# blahblahVCA.net
KiCad netlist of a schematic drawn in EAGLE
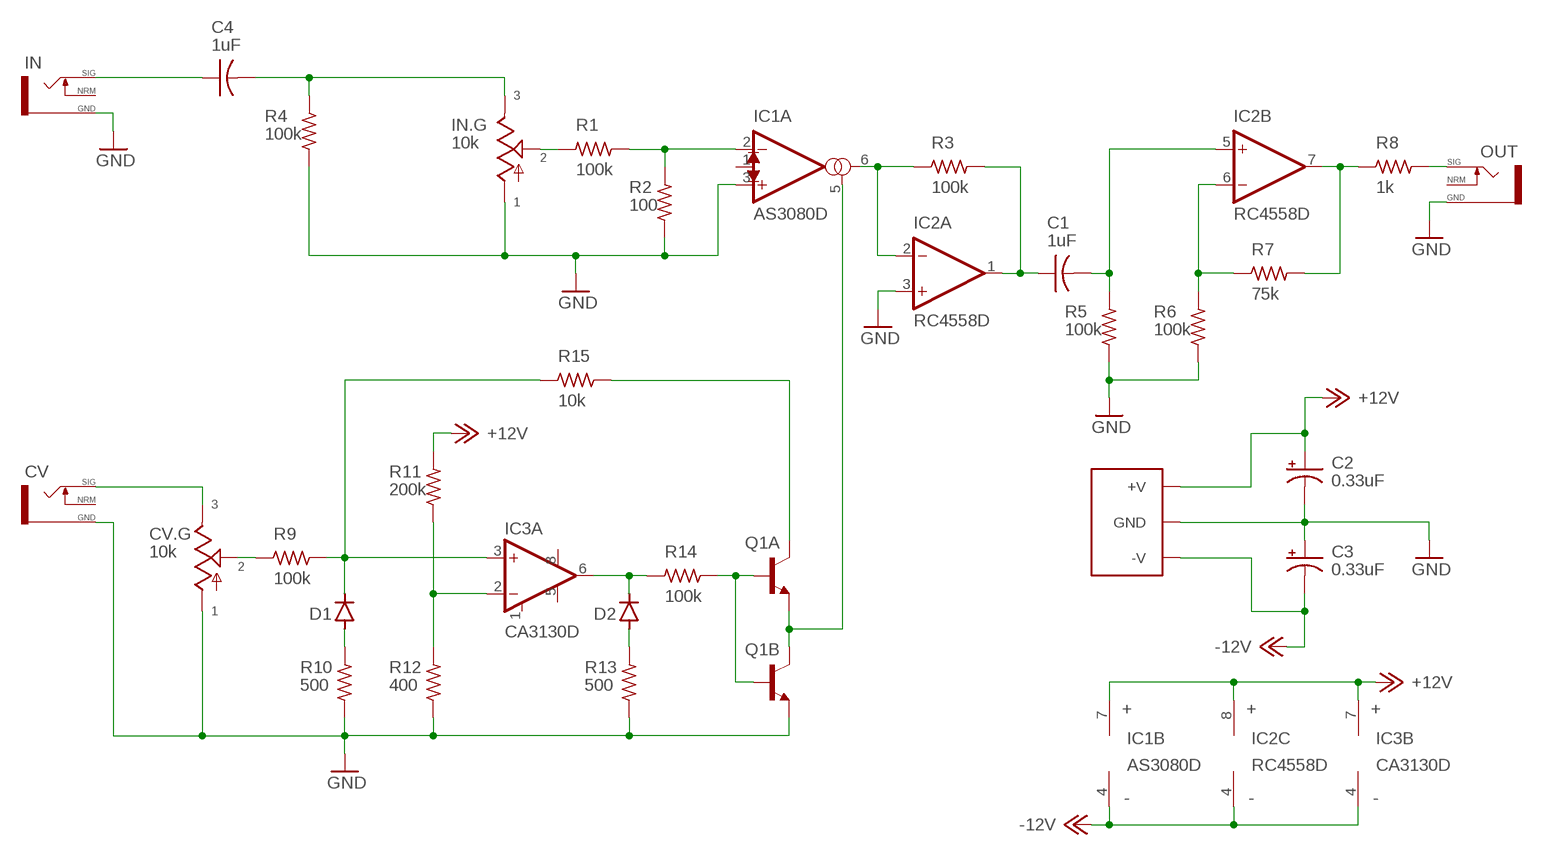
[diagram p0: schematic, sheet 1]

(export (version "E")
  (design (tool "Eeschema 10.0.6"))
  (components
    (comp (ref "C1")
      (value "1uF")
      (footprint "eagle-import:C05")
      (libsource (lib "eagle-import") (part "C-05"))
    )
    (comp (ref "C2")
      (value "0.33uF")
      (footprint "eagle-import:E025")
      (libsource (lib "eagle-import") (part "CPOL-E025"))
    )
    (comp (ref "C3")
      (value "0.33uF")
      (footprint "eagle-import:E025")
      (libsource (lib "eagle-import") (part "CPOL-E025"))
    )
    (comp (ref "C4")
      (value "1uF")
      (footprint "eagle-import:C05")
      (libsource (lib "eagle-import") (part "C-05"))
    )
    (comp (ref "CV")
      (value "MONO301M")
      (footprint "eagle-import:PJ301M")
      (libsource (lib "eagle-import") (part "MONO301M"))
    )
    (comp (ref "CV.G")
      (value "10k")
      (footprint "eagle-import:ALPHA-VERT")
      (libsource (lib "eagle-import") (part "PALPHA"))
    )
    (comp (ref "D1")
      (value "1N914")
      (footprint "eagle-import:DO35-7")
      (libsource (lib "eagle-import") (part "1N914"))
    )
    (comp (ref "D2")
      (value "1N914")
      (footprint "eagle-import:DO35-7")
      (libsource (lib "eagle-import") (part "1N914"))
    )
    (comp (ref "IC1")
      (value "AS3080D")
      (footprint "eagle-import:DIL08")
      (libsource (lib "eagle-import") (part "AS3080D"))
    )
    (comp (ref "IC2")
      (value "RC4558D")
      (footprint "eagle-import:DIL08")
      (libsource (lib "eagle-import") (part "RC4558D"))
    )
    (comp (ref "IC3")
      (value "CA3130D")
      (footprint "eagle-import:DIL08")
      (libsource (lib "eagle-import") (part "CA3130D"))
    )
    (comp (ref "IN")
      (value "MONO301M")
      (footprint "eagle-import:PJ301M")
      (libsource (lib "eagle-import") (part "MONO301M"))
    )
    (comp (ref "IN.G")
      (value "10k")
      (footprint "eagle-import:ALPHA-VERT")
      (libsource (lib "eagle-import") (part "PALPHA"))
    )
    (comp (ref "OUT")
      (value "MONO301M")
      (footprint "eagle-import:PJ301M")
      (libsource (lib "eagle-import") (part "MONO301M"))
    )
    (comp (ref "Q1")
      (value "BCM847DS")
      (footprint "eagle-import:SOT-23-6")
      (libsource (lib "eagle-import") (part "BCM847DS"))
    )
    (comp (ref "R1")
      (value "100k")
      (footprint "eagle-import:R1206")
      (libsource (lib "eagle-import") (part "R-1206"))
    )
    (comp (ref "R2")
      (value "100")
      (footprint "eagle-import:R1206")
      (libsource (lib "eagle-import") (part "R-1206"))
    )
    (comp (ref "R3")
      (value "100k")
      (footprint "eagle-import:R1206")
      (libsource (lib "eagle-import") (part "R-1206"))
    )
    (comp (ref "R4")
      (value "100k")
      (footprint "eagle-import:R1206")
      (libsource (lib "eagle-import") (part "R-1206"))
    )
    (comp (ref "R5")
      (value "100k")
      (footprint "eagle-import:R1206")
      (libsource (lib "eagle-import") (part "R-1206"))
    )
    (comp (ref "R6")
      (value "100k")
      (footprint "eagle-import:R1206")
      (libsource (lib "eagle-import") (part "R-1206"))
    )
    (comp (ref "R7")
      (value "75k")
      (footprint "eagle-import:R1206")
      (libsource (lib "eagle-import") (part "R-1206"))
    )
    (comp (ref "R8")
      (value "1k")
      (footprint "eagle-import:R1206")
      (libsource (lib "eagle-import") (part "R-1206"))
    )
    (comp (ref "R9")
      (value "100k")
      (footprint "eagle-import:R1206")
      (libsource (lib "eagle-import") (part "R-1206"))
    )
    (comp (ref "R10")
      (value "500")
      (footprint "eagle-import:R1206")
      (libsource (lib "eagle-import") (part "R-1206"))
    )
    (comp (ref "R11")
      (value "200k")
      (footprint "eagle-import:R1206")
      (libsource (lib "eagle-import") (part "R-1206"))
    )
    (comp (ref "R12")
      (value "400")
      (footprint "eagle-import:R1206")
      (libsource (lib "eagle-import") (part "R-1206"))
    )
    (comp (ref "R13")
      (value "500")
      (footprint "eagle-import:R1206")
      (libsource (lib "eagle-import") (part "R-1206"))
    )
    (comp (ref "R14")
      (value "100k")
      (footprint "eagle-import:R1206")
      (libsource (lib "eagle-import") (part "R-1206"))
    )
    (comp (ref "R15")
      (value "10k")
      (footprint "eagle-import:R1206")
      (libsource (lib "eagle-import") (part "R-1206"))
    )
    (comp (ref "U$1")
      (value "10PIN-PWR")
      (footprint "eagle-import:10PIN-HEADER")
      (libsource (lib "eagle-import") (part "10PIN-PWR"))
    )
  )
  (nets
    (net (code "1") (name "+12V") (class "Default")
      (node (ref "C2") (pin "+") (pinfunction "+_+") (pintype "passive"))
      (node (ref "IC1") (pin "7") (pinfunction "V+_7") (pintype "power_in"))
      (node (ref "IC2") (pin "8") (pinfunction "V+_8") (pintype "power_in"))
      (node (ref "IC3") (pin "7") (pinfunction "V+_7") (pintype "power_in"))
      (node (ref "R11") (pin "2") (pinfunction "2_2") (pintype "passive"))
      (node (ref "U$1") (pin "10") (pinfunction "+V_10") (pintype "bidirectional"))
      (node (ref "U$1") (pin "9") (pinfunction "+V_9") (pintype "bidirectional"))
    )
    (net (code "2") (name "-12V") (class "Default")
      (node (ref "C3") (pin "-") (pinfunction "-_-") (pintype "passive"))
      (node (ref "IC1") (pin "4") (pinfunction "V-_4") (pintype "power_in"))
      (node (ref "IC2") (pin "4") (pinfunction "V-_4") (pintype "power_in"))
      (node (ref "IC3") (pin "4") (pinfunction "V-_4") (pintype "power_in"))
      (node (ref "U$1") (pin "1") (pinfunction "-V_1") (pintype "bidirectional"))
      (node (ref "U$1") (pin "2") (pinfunction "-V_2") (pintype "bidirectional"))
    )
    (net (code "3") (name "GND") (class "Default")
      (node (ref "C2") (pin "-") (pinfunction "-_-") (pintype "passive"))
      (node (ref "C3") (pin "+") (pinfunction "+_+") (pintype "passive"))
      (node (ref "CV") (pin "SLV") (pinfunction "SLEEVE-GND_SLV") (pintype "passive"))
      (node (ref "CV.G") (pin "1") (pinfunction "1_1") (pintype "passive"))
      (node (ref "IC1") (pin "3") (pinfunction "NON-INVERTING(+)_3") (pintype "input"))
      (node (ref "IC2") (pin "3") (pinfunction "NON-INVERTING(+)_3") (pintype "input"))
      (node (ref "IN") (pin "SLV") (pinfunction "SLEEVE-GND_SLV") (pintype "passive"))
      (node (ref "IN.G") (pin "1") (pinfunction "1_1") (pintype "passive"))
      (node (ref "OUT") (pin "SLV") (pinfunction "SLEEVE-GND_SLV") (pintype "passive"))
      (node (ref "Q1") (pin "4") (pinfunction "E_4") (pintype "bidirectional"))
      (node (ref "R10") (pin "1") (pinfunction "1_1") (pintype "passive"))
      (node (ref "R12") (pin "1") (pinfunction "1_1") (pintype "passive"))
      (node (ref "R13") (pin "1") (pinfunction "1_1") (pintype "passive"))
      (node (ref "R2") (pin "1") (pinfunction "1_1") (pintype "passive"))
      (node (ref "R4") (pin "1") (pinfunction "1_1") (pintype "passive"))
      (node (ref "R5") (pin "1") (pinfunction "1_1") (pintype "passive"))
      (node (ref "R6") (pin "1") (pinfunction "1_1") (pintype "passive"))
      (node (ref "U$1") (pin "3") (pinfunction "GND_3") (pintype "bidirectional"))
      (node (ref "U$1") (pin "4") (pinfunction "GND_4") (pintype "bidirectional"))
      (node (ref "U$1") (pin "5") (pinfunction "GND_5") (pintype "bidirectional"))
      (node (ref "U$1") (pin "6") (pinfunction "GND_6") (pintype "bidirectional"))
      (node (ref "U$1") (pin "7") (pinfunction "GND_7") (pintype "bidirectional"))
      (node (ref "U$1") (pin "8") (pinfunction "GND_8") (pintype "bidirectional"))
    )
    (net (code "4") (name "Net-(C4-Pad2)") (class "Default")
      (node (ref "C4") (pin "2") (pinfunction "2_2") (pintype "passive"))
      (node (ref "IN.G") (pin "3") (pinfunction "3_3") (pintype "passive"))
      (node (ref "R4") (pin "2") (pinfunction "2_2") (pintype "passive"))
    )
    (net (code "5") (name "Net-(CV-TIP-SIG)") (class "Default")
      (node (ref "CV") (pin "TIP") (pinfunction "TIP-SIG_TIP") (pintype "passive"))
      (node (ref "CV.G") (pin "3") (pinfunction "3_3") (pintype "passive"))
    )
    (net (code "6") (name "Net-(CV.G-Pad2)") (class "Default")
      (node (ref "CV.G") (pin "2") (pinfunction "2_2") (pintype "passive"))
      (node (ref "R9") (pin "1") (pinfunction "1_1") (pintype "passive"))
    )
    (net (code "7") (name "Net-(D1-PadA)") (class "Default")
      (node (ref "D1") (pin "A") (pinfunction "A_A") (pintype "passive"))
      (node (ref "R10") (pin "2") (pinfunction "2_2") (pintype "passive"))
    )
    (net (code "8") (name "Net-(D2-PadA)") (class "Default")
      (node (ref "D2") (pin "A") (pinfunction "A_A") (pintype "passive"))
      (node (ref "R13") (pin "2") (pinfunction "2_2") (pintype "passive"))
    )
    (net (code "9") (name "Net-(IC1A-I-BIAS)") (class "Default")
      (node (ref "IC1") (pin "5") (pinfunction "I-BIAS_5") (pintype "input"))
      (node (ref "Q1") (pin "1") (pinfunction "E_1") (pintype "bidirectional"))
      (node (ref "Q1") (pin "3") (pinfunction "C_3") (pintype "bidirectional"))
    )
    (net (code "10") (name "Net-(IC1A-INVERTING(-))") (class "Default")
      (node (ref "IC1") (pin "2") (pinfunction "INVERTING(-)_2") (pintype "input"))
      (node (ref "R1") (pin "2") (pinfunction "2_2") (pintype "passive"))
      (node (ref "R2") (pin "2") (pinfunction "2_2") (pintype "passive"))
    )
    (net (code "11") (name "Net-(IC1A-OUT)") (class "Default")
      (node (ref "IC1") (pin "6") (pinfunction "OUT_6") (pintype "output"))
      (node (ref "IC2") (pin "2") (pinfunction "INVERTING(-)_2") (pintype "input"))
      (node (ref "R3") (pin "1") (pinfunction "1_1") (pintype "passive"))
    )
    (net (code "12") (name "Net-(IC2A-OUT)") (class "Default")
      (node (ref "C1") (pin "1") (pinfunction "1_1") (pintype "passive"))
      (node (ref "IC2") (pin "1") (pinfunction "OUT_1") (pintype "output"))
      (node (ref "R3") (pin "2") (pinfunction "2_2") (pintype "passive"))
    )
    (net (code "13") (name "Net-(IC2B-INVERTING(-))") (class "Default")
      (node (ref "IC2") (pin "6") (pinfunction "INVERTING(-)_6") (pintype "input"))
      (node (ref "R6") (pin "2") (pinfunction "2_2") (pintype "passive"))
      (node (ref "R7") (pin "1") (pinfunction "1_1") (pintype "passive"))
    )
    (net (code "14") (name "Net-(IC2B-NON-INVERTING(+))") (class "Default")
      (node (ref "C1") (pin "2") (pinfunction "2_2") (pintype "passive"))
      (node (ref "IC2") (pin "5") (pinfunction "NON-INVERTING(+)_5") (pintype "input"))
      (node (ref "R5") (pin "2") (pinfunction "2_2") (pintype "passive"))
    )
    (net (code "15") (name "Net-(IC2B-OUT)") (class "Default")
      (node (ref "IC2") (pin "7") (pinfunction "OUT_7") (pintype "output"))
      (node (ref "R7") (pin "2") (pinfunction "2_2") (pintype "passive"))
      (node (ref "R8") (pin "1") (pinfunction "1_1") (pintype "passive"))
    )
    (net (code "16") (name "Net-(IC3A-INVERTINGA(-))") (class "Default")
      (node (ref "IC3") (pin "2") (pinfunction "INVERTINGA(-)_2") (pintype "input"))
      (node (ref "R11") (pin "1") (pinfunction "1_1") (pintype "passive"))
      (node (ref "R12") (pin "2") (pinfunction "2_2") (pintype "passive"))
    )
    (net (code "17") (name "Net-(IC3A-NON-INVERTING(+))") (class "Default")
      (node (ref "D1") (pin "C") (pinfunction "C_C") (pintype "passive"))
      (node (ref "IC3") (pin "3") (pinfunction "NON-INVERTING(+)_3") (pintype "input"))
      (node (ref "R15") (pin "1") (pinfunction "1_1") (pintype "passive"))
      (node (ref "R9") (pin "2") (pinfunction "2_2") (pintype "passive"))
    )
    (net (code "18") (name "Net-(IC3A-OUT)") (class "Default")
      (node (ref "D2") (pin "C") (pinfunction "C_C") (pintype "passive"))
      (node (ref "IC3") (pin "6") (pinfunction "OUT_6") (pintype "output"))
      (node (ref "R14") (pin "1") (pinfunction "1_1") (pintype "passive"))
    )
    (net (code "19") (name "Net-(IN-TIP-SIG)") (class "Default")
      (node (ref "C4") (pin "1") (pinfunction "1_1") (pintype "passive"))
      (node (ref "IN") (pin "TIP") (pinfunction "TIP-SIG_TIP") (pintype "passive"))
    )
    (net (code "20") (name "Net-(IN.G-Pad2)") (class "Default")
      (node (ref "IN.G") (pin "2") (pinfunction "2_2") (pintype "passive"))
      (node (ref "R1") (pin "1") (pinfunction "1_1") (pintype "passive"))
    )
    (net (code "21") (name "Net-(OUT-TIP-SIG)") (class "Default")
      (node (ref "OUT") (pin "TIP") (pinfunction "TIP-SIG_TIP") (pintype "passive"))
      (node (ref "R8") (pin "2") (pinfunction "2_2") (pintype "passive"))
    )
    (net (code "22") (name "Net-(Q1A-B)") (class "Default")
      (node (ref "Q1") (pin "2") (pinfunction "B_2") (pintype "bidirectional"))
      (node (ref "Q1") (pin "5") (pinfunction "B_5") (pintype "bidirectional"))
      (node (ref "R14") (pin "2") (pinfunction "2_2") (pintype "passive"))
    )
    (net (code "23") (name "Net-(Q1A-C)") (class "Default")
      (node (ref "Q1") (pin "6") (pinfunction "C_6") (pintype "bidirectional"))
      (node (ref "R15") (pin "2") (pinfunction "2_2") (pintype "passive"))
    )
    (net (code "24") (name "unconnected-(CV-SWITCH-NORM-PadSW)") (class "Default")
      (node (ref "CV") (pin "SW") (pinfunction "SWITCH-NORM_SW") (pintype "passive"))
    )
    (net (code "25") (name "unconnected-(IC1A-D-BIAS-Pad1)") (class "Default")
      (node (ref "IC1") (pin "1") (pinfunction "D-BIAS_1") (pintype "input"))
    )
    (net (code "26") (name "unconnected-(IC3A-NULL(1)-Pad1)") (class "Default")
      (node (ref "IC3") (pin "1") (pinfunction "NULL(1)_1") (pintype "input"))
    )
    (net (code "27") (name "unconnected-(IC3A-NULL(5)-Pad5)") (class "Default")
      (node (ref "IC3") (pin "5") (pinfunction "NULL(5)_5") (pintype "input"))
    )
    (net (code "28") (name "unconnected-(IC3A-STRB-Pad8)") (class "Default")
      (node (ref "IC3") (pin "8") (pinfunction "STRB_8") (pintype "input"))
    )
    (net (code "29") (name "unconnected-(IN-SWITCH-NORM-PadSW)") (class "Default")
      (node (ref "IN") (pin "SW") (pinfunction "SWITCH-NORM_SW") (pintype "passive"))
    )
    (net (code "30") (name "unconnected-(OUT-SWITCH-NORM-PadSW)") (class "Default")
      (node (ref "OUT") (pin "SW") (pinfunction "SWITCH-NORM_SW") (pintype "passive"))
    )
  )
)
